# system.net
KiCad netlist of a schematic drawn in Altium Designer
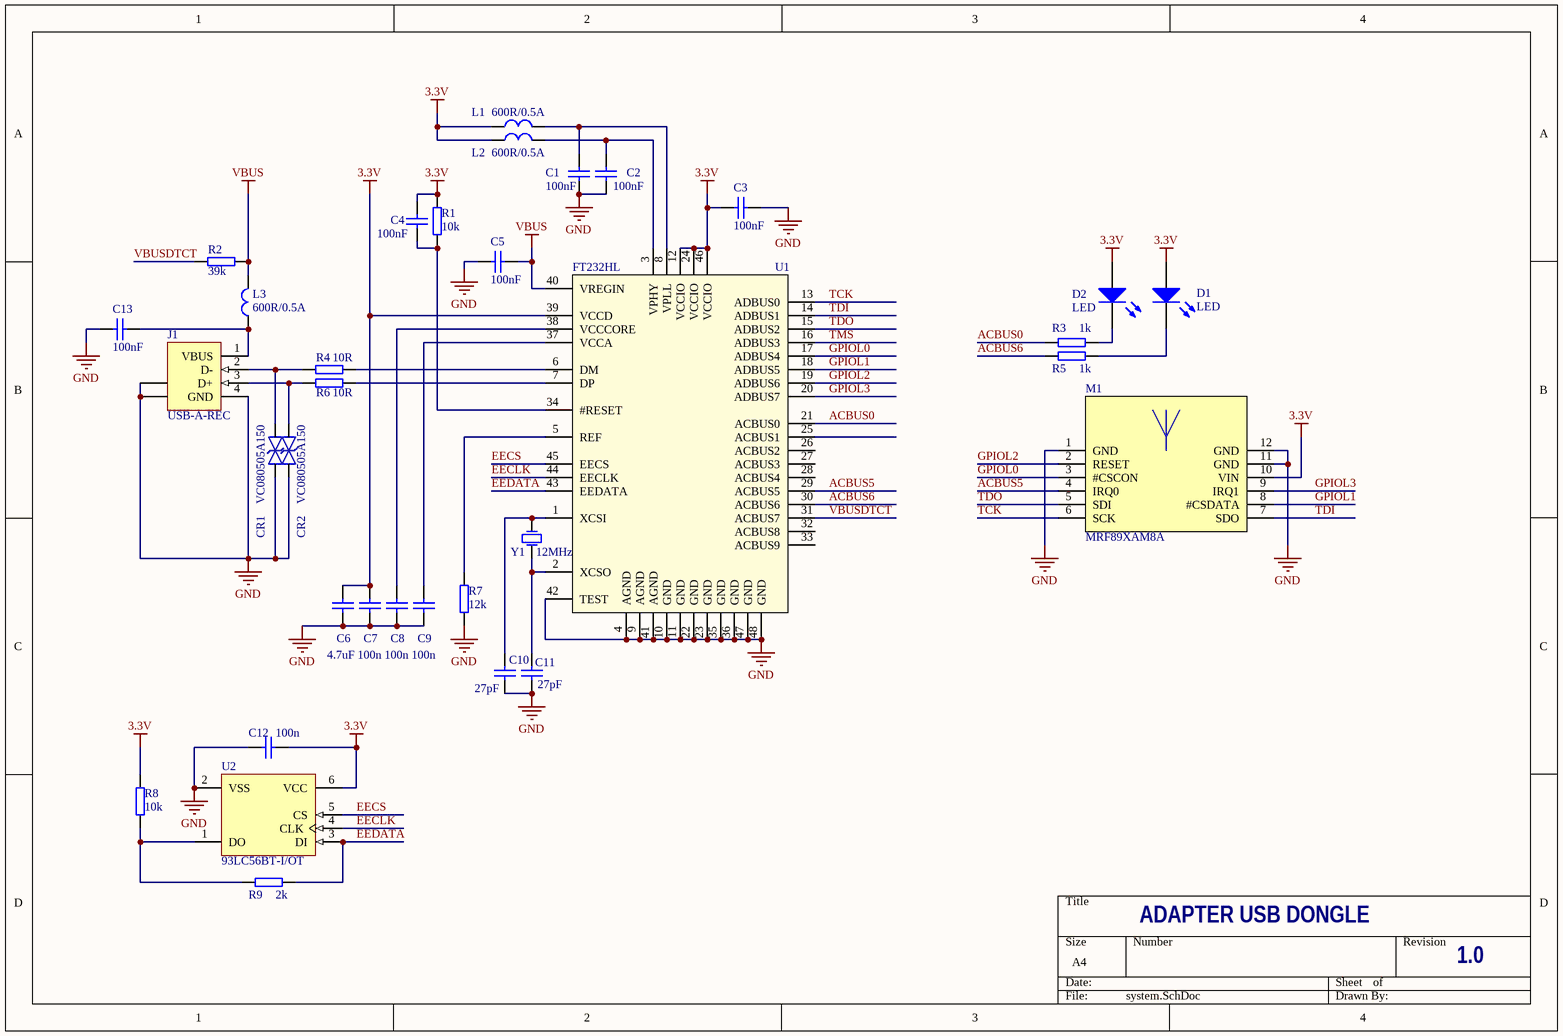
[diagram p0: system.SchDoc]

(export (version "E")
  (design (tool "Eeschema 10.0.6"))
  (components
    (comp (ref "C1")
      (value "100nF")
      (footprint "C0805")
      (description "Capacitor")
      (fields (field (name "PUBLISHER") "Altium Limited"))
      (libsource (lib "ANY Devices") (part "Cap"))
    )
    (comp (ref "C2")
      (value "100nF")
      (footprint "C0805")
      (description "Capacitor")
      (fields (field (name "PUBLISHER") "Altium Limited"))
      (libsource (lib "ANY Devices") (part "Cap"))
    )
    (comp (ref "C3")
      (value "100nF")
      (footprint "C0805")
      (description "Capacitor")
      (fields (field (name "PUBLISHER") "Altium Limited"))
      (libsource (lib "ANY Devices") (part "Cap"))
    )
    (comp (ref "C4")
      (value "100nF")
      (footprint "C0805")
      (description "Capacitor")
      (fields (field (name "PUBLISHER") "Altium Limited"))
      (libsource (lib "ANY Devices") (part "Cap"))
    )
    (comp (ref "C5")
      (value "100nF")
      (footprint "C0805")
      (description "Capacitor")
      (fields (field (name "PUBLISHER") "Altium Limited"))
      (libsource (lib "ANY Devices") (part "Cap"))
    )
    (comp (ref "C6")
      (value "4.7uF")
      (footprint "C0805")
      (description "Capacitor")
      (fields (field (name "PUBLISHER") "Altium Limited"))
      (libsource (lib "ANY Devices") (part "Cap"))
    )
    (comp (ref "C7")
      (value "100n")
      (footprint "C0805")
      (description "Capacitor")
      (fields (field (name "PUBLISHER") "Altium Limited"))
      (libsource (lib "ANY Devices") (part "Cap"))
    )
    (comp (ref "C8")
      (value "100n")
      (footprint "C0805")
      (description "Capacitor")
      (fields (field (name "PUBLISHER") "Altium Limited"))
      (libsource (lib "ANY Devices") (part "Cap"))
    )
    (comp (ref "C9")
      (value "100n")
      (footprint "C0805")
      (description "Capacitor")
      (fields (field (name "PUBLISHER") "Altium Limited"))
      (libsource (lib "ANY Devices") (part "Cap"))
    )
    (comp (ref "C10")
      (value "27pF")
      (footprint "C0805")
      (description "Capacitor")
      (fields (field (name "PUBLISHER") "Altium Limited"))
      (libsource (lib "ANY Devices") (part "Cap"))
    )
    (comp (ref "C11")
      (value "27pF")
      (footprint "C0805")
      (description "Capacitor")
      (fields (field (name "PUBLISHER") "Altium Limited"))
      (libsource (lib "ANY Devices") (part "Cap"))
    )
    (comp (ref "C12")
      (value "100n")
      (footprint "C0805")
      (description "Capacitor")
      (fields (field (name "PUBLISHER") "Altium Limited"))
      (libsource (lib "ANY Devices") (part "Cap"))
    )
    (comp (ref "C13")
      (value "100nF")
      (footprint "C0805")
      (description "Capacitor")
      (fields (field (name "Comment") "10nF") (field (name "PUBLISHER") "Altium Limited"))
      (libsource (lib "ANY Devices") (part "Cap"))
    )
    (comp (ref "CR1")
      (value "VC080505A150")
      (footprint "R0805")
      (description "Multilayer Ceramic Transient Voltage Suppressors")
      (libsource (lib "ANY Devices") (part "ESD Protection"))
    )
    (comp (ref "CR2")
      (value "VC080505A150")
      (footprint "R0805")
      (description "Multilayer Ceramic Transient Voltage Suppressors")
      (libsource (lib "ANY Devices") (part "ESD Protection"))
    )
    (comp (ref "D1")
      (value "LED")
      (footprint "D0805")
      (description "Typical RED, GREEN, YELLOW, AMBER GaAs LED")
      (fields (field (name "PUBLISHER") "Altium Limited"))
      (libsource (lib "ANY Devices") (part "LED2"))
    )
    (comp (ref "D2")
      (value "LED")
      (footprint "D0805")
      (description "Typical RED, GREEN, YELLOW, AMBER GaAs LED")
      (fields (field (name "PUBLISHER") "Altium Limited"))
      (libsource (lib "ANY Devices") (part "LED2"))
    )
    (comp (ref "J1")
      (value "USB-A-REC")
      (footprint "USB/SM2.5-4H4A")
      (description "USB 1.1, Right Angle, Thru-Hole, Reverse Type, 4 Position, Black")
      (libsource (lib "ANY Connectors") (part "USB-A_MALE"))
    )
    (comp (ref "L1")
      (value "600R/0.5A")
      (footprint "L0805")
      (description "Inductor Ferrite Bead, BLM18PG")
      (fields (field (name "PUBLISHER") "Altium Limited"))
      (libsource (lib "ANY Devices") (part "Inductor Ferrite Bead"))
    )
    (comp (ref "L2")
      (value "600R/0.5A")
      (footprint "L0805")
      (description "Inductor Ferrite Bead, BLM18PG")
      (fields (field (name "PUBLISHER") "Altium Limited"))
      (libsource (lib "ANY Devices") (part "Inductor Ferrite Bead"))
    )
    (comp (ref "L3")
      (value "600R/0.5A")
      (footprint "L0805")
      (description "Inductor Ferrite Bead, BLM18PG")
      (fields (field (name "PUBLISHER") "Altium Limited"))
      (libsource (lib "ANY Devices") (part "Inductor Ferrite Bead"))
    )
    (comp (ref "M1")
      (value "MRF89XAM8A")
      (footprint "MRF89XAM8A")
      (description "868 MHz Ultra-Low Power  Sub-GHz Transceiver Module")
      (libsource (lib "Modules") (part "MRF89XAM8A"))
    )
    (comp (ref "R1")
      (value "10k")
      (footprint "R0805")
      (description "Resistor")
      (fields (field (name "PUBLISHER") "Altium Limited"))
      (libsource (lib "") (part "Res2_1"))
    )
    (comp (ref "R2")
      (value "39k")
      (footprint "R0805")
      (description "Resistor")
      (fields (field (name "PUBLISHER") "Altium Limited"))
      (libsource (lib "ANY Devices") (part "Res2"))
    )
    (comp (ref "R3")
      (value "1k")
      (footprint "R0805")
      (description "Resistor")
      (fields (field (name "PUBLISHER") "Altium Limited"))
      (libsource (lib "") (part "Res2_2"))
    )
    (comp (ref "R4")
      (value "10R")
      (footprint "R0805")
      (description "Resistor")
      (fields (field (name "PUBLISHER") "Altium Limited"))
      (libsource (lib "") (part "Res2_2"))
    )
    (comp (ref "R5")
      (value "1k")
      (footprint "R0805")
      (description "Resistor")
      (fields (field (name "PUBLISHER") "Altium Limited"))
      (libsource (lib "") (part "Res2_2"))
    )
    (comp (ref "R6")
      (value "10R")
      (footprint "R0805")
      (description "Resistor")
      (fields (field (name "PUBLISHER") "Altium Limited"))
      (libsource (lib "") (part "Res2_1"))
    )
    (comp (ref "R7")
      (value "12k")
      (footprint "R0805")
      (description "Resistor")
      (fields (field (name "PUBLISHER") "Altium Limited"))
      (libsource (lib "") (part "Res2_1"))
    )
    (comp (ref "R8")
      (value "10k")
      (footprint "R0805")
      (description "Resistor")
      (fields (field (name "PUBLISHER") "Altium Limited"))
      (libsource (lib "") (part "Res2_1"))
    )
    (comp (ref "R9")
      (value "2k")
      (footprint "R0805")
      (description "Resistor")
      (fields (field (name "PUBLISHER") "Altium Limited"))
      (libsource (lib "ANY Devices") (part "Res2"))
    )
    (comp (ref "U1")
      (value "FT232HL")
      (footprint "LQFP-48_M")
      (description "Single Channel HiSpeed USB to Multipurpose   UART/FIFO IC")
      (libsource (lib "ANYlib") (part "FT232HL"))
    )
    (comp (ref "U2")
      (value "93LC56BT-I/OT")
      (footprint "SOT-23-OT6_N")
      (description "2K, 128x16-bit, 2.5V Microwire Serial EEPROM, 6-Pin SOT-23, Industrial Temperature, Tape and Reel")
      (fields (field (name "PUBLISHER") "Altium Limited"))
      (libsource (lib "ANYlib") (part "93LC56BT-I/OT"))
    )
    (comp (ref "Y1")
      (value "12MHz")
      (footprint "OSC 5.0X3.2")
      (description "Crystal")
      (fields (field (name "PUBLISHER") "Altium Limited"))
      (libsource (lib "ANY Devices") (part "XTAL_ABM3"))
    )
  )
  (nets
    (net (code "1") (name "/ACBUS0") (class "Default")
      (node (ref "R3") (pin "1") (pinfunction "1_1") (pintype "passive"))
      (node (ref "U1") (pin "21") (pinfunction "ACBUS0_21") (pintype "passive"))
    )
    (net (code "2") (name "/ACBUS5") (class "Default")
      (node (ref "M1") (pin "4") (pinfunction "IRQ0_4") (pintype "passive"))
      (node (ref "U1") (pin "29") (pinfunction "ACBUS5_29") (pintype "passive"))
    )
    (net (code "3") (name "/ACBUS6") (class "Default")
      (node (ref "R5") (pin "1") (pinfunction "1_1") (pintype "passive"))
      (node (ref "U1") (pin "30") (pinfunction "ACBUS6_30") (pintype "passive"))
    )
    (net (code "4") (name "/EECLK") (class "Default")
      (node (ref "U1") (pin "44") (pinfunction "EECLK_44") (pintype "passive"))
      (node (ref "U2") (pin "4") (pinfunction "CLK_4") (pintype "input"))
    )
    (net (code "5") (name "/EECS") (class "Default")
      (node (ref "U1") (pin "45") (pinfunction "EECS_45") (pintype "passive"))
      (node (ref "U2") (pin "5") (pinfunction "CS_5") (pintype "input"))
    )
    (net (code "6") (name "/EEDATA") (class "Default")
      (node (ref "R9") (pin "1") (pinfunction "1_1") (pintype "passive"))
      (node (ref "U1") (pin "43") (pinfunction "EEDATA_43") (pintype "passive"))
      (node (ref "U2") (pin "3") (pinfunction "DI_3") (pintype "input"))
    )
    (net (code "7") (name "/GPIOL0") (class "Default")
      (node (ref "M1") (pin "3") (pinfunction "#CSCON_3") (pintype "passive"))
      (node (ref "U1") (pin "17") (pinfunction "ADBUS4_17") (pintype "passive"))
    )
    (net (code "8") (name "/GPIOL1") (class "Default")
      (node (ref "M1") (pin "8") (pinfunction "#CSDATA_8") (pintype "passive"))
      (node (ref "U1") (pin "18") (pinfunction "ADBUS5_18") (pintype "passive"))
    )
    (net (code "9") (name "/GPIOL2") (class "Default")
      (node (ref "M1") (pin "2") (pinfunction "RESET_2") (pintype "passive"))
      (node (ref "U1") (pin "19") (pinfunction "ADBUS6_19") (pintype "passive"))
    )
    (net (code "10") (name "/GPIOL3") (class "Default")
      (node (ref "M1") (pin "9") (pinfunction "IRQ1_9") (pintype "passive"))
      (node (ref "U1") (pin "20") (pinfunction "ADBUS7_20") (pintype "passive"))
    )
    (net (code "11") (name "/TCK") (class "Default")
      (node (ref "M1") (pin "6") (pinfunction "SCK_6") (pintype "passive"))
      (node (ref "U1") (pin "13") (pinfunction "ADBUS0_13") (pintype "passive"))
    )
    (net (code "12") (name "/TDI") (class "Default")
      (node (ref "M1") (pin "7") (pinfunction "SDO_7") (pintype "passive"))
      (node (ref "U1") (pin "14") (pinfunction "ADBUS1_14") (pintype "passive"))
    )
    (net (code "13") (name "/TDO") (class "Default")
      (node (ref "M1") (pin "5") (pinfunction "SDI_5") (pintype "passive"))
      (node (ref "U1") (pin "15") (pinfunction "ADBUS2_15") (pintype "passive"))
    )
    (net (code "14") (name "/TMS") (class "Default")
      (node (ref "U1") (pin "16") (pinfunction "ADBUS3_16") (pintype "passive"))
    )
    (net (code "15") (name "/VBUSDTCT") (class "Default")
      (node (ref "R2") (pin "2") (pinfunction "2_2") (pintype "passive"))
      (node (ref "U1") (pin "31") (pinfunction "ACBUS7_31") (pintype "passive"))
    )
    (net (code "16") (name "3.3V") (class "Default")
      (node (ref "C12") (pin "2") (pinfunction "2_2") (pintype "passive"))
      (node (ref "C3") (pin "2") (pinfunction "2_2") (pintype "passive"))
      (node (ref "C4") (pin "1") (pinfunction "1_1") (pintype "passive"))
      (node (ref "C6") (pin "1") (pinfunction "1_1") (pintype "passive"))
      (node (ref "C7") (pin "1") (pinfunction "1_1") (pintype "passive"))
      (node (ref "D1") (pin "1") (pinfunction "A_1") (pintype "passive"))
      (node (ref "D2") (pin "1") (pinfunction "A_1") (pintype "passive"))
      (node (ref "L1") (pin "1") (pinfunction "1_1") (pintype "passive"))
      (node (ref "L2") (pin "1") (pinfunction "1_1") (pintype "passive"))
      (node (ref "M1") (pin "10") (pinfunction "VIN_10") (pintype "passive"))
      (node (ref "R1") (pin "2") (pinfunction "2_2") (pintype "passive"))
      (node (ref "R8") (pin "2") (pinfunction "2_2") (pintype "passive"))
      (node (ref "U1") (pin "12") (pinfunction "VCCIO_12") (pintype "passive"))
      (node (ref "U1") (pin "24") (pinfunction "VCCIO_24") (pintype "passive"))
      (node (ref "U1") (pin "39") (pinfunction "VCCD_39") (pintype "passive"))
      (node (ref "U1") (pin "46") (pinfunction "VCCIO_46") (pintype "passive"))
      (node (ref "U2") (pin "6") (pinfunction "VCC_6") (pintype "power_in"))
    )
    (net (code "17") (name "GND") (class "Default")
      (node (ref "C1") (pin "2") (pinfunction "2_2") (pintype "passive"))
      (node (ref "C10") (pin "2") (pinfunction "2_2") (pintype "passive"))
      (node (ref "C11") (pin "2") (pinfunction "2_2") (pintype "passive"))
      (node (ref "C12") (pin "1") (pinfunction "1_1") (pintype "passive"))
      (node (ref "C13") (pin "1") (pinfunction "1_1") (pintype "passive"))
      (node (ref "C2") (pin "2") (pinfunction "2_2") (pintype "passive"))
      (node (ref "C3") (pin "1") (pinfunction "1_1") (pintype "passive"))
      (node (ref "C5") (pin "2") (pinfunction "2_2") (pintype "passive"))
      (node (ref "C6") (pin "2") (pinfunction "2_2") (pintype "passive"))
      (node (ref "C7") (pin "2") (pinfunction "2_2") (pintype "passive"))
      (node (ref "C8") (pin "2") (pinfunction "2_2") (pintype "passive"))
      (node (ref "C9") (pin "2") (pinfunction "2_2") (pintype "passive"))
      (node (ref "CR1") (pin "1") (pinfunction "1_1") (pintype "passive"))
      (node (ref "CR2") (pin "1") (pinfunction "1_1") (pintype "passive"))
      (node (ref "J1") (pin "4") (pinfunction "GND_4") (pintype "power_in"))
      (node (ref "J1") (pin "5") (pinfunction "SHLD_5") (pintype "passive"))
      (node (ref "J1") (pin "6") (pinfunction "SHLD_6") (pintype "passive"))
      (node (ref "M1") (pin "1") (pinfunction "GND_1") (pintype "passive"))
      (node (ref "M1") (pin "11") (pinfunction "GND_11") (pintype "passive"))
      (node (ref "M1") (pin "12") (pinfunction "GND_12") (pintype "passive"))
      (node (ref "R7") (pin "1") (pinfunction "1_1") (pintype "passive"))
      (node (ref "U1") (pin "10") (pinfunction "GND_10") (pintype "passive"))
      (node (ref "U1") (pin "11") (pinfunction "GND_11") (pintype "passive"))
      (node (ref "U1") (pin "22") (pinfunction "GND_22") (pintype "passive"))
      (node (ref "U1") (pin "23") (pinfunction "GND_23") (pintype "passive"))
      (node (ref "U1") (pin "35") (pinfunction "GND_35") (pintype "passive"))
      (node (ref "U1") (pin "36") (pinfunction "GND_36") (pintype "passive"))
      (node (ref "U1") (pin "4") (pinfunction "AGND_4") (pintype "passive"))
      (node (ref "U1") (pin "41") (pinfunction "AGND_41") (pintype "passive"))
      (node (ref "U1") (pin "42") (pinfunction "TEST_42") (pintype "passive"))
      (node (ref "U1") (pin "47") (pinfunction "GND_47") (pintype "passive"))
      (node (ref "U1") (pin "48") (pinfunction "GND_48") (pintype "passive"))
      (node (ref "U1") (pin "9") (pinfunction "AGND_9") (pintype "passive"))
      (node (ref "U2") (pin "2") (pinfunction "VSS_2") (pintype "power_in"))
    )
    (net (code "18") (name "Net-(D1-K)") (class "Default")
      (node (ref "D1") (pin "2") (pinfunction "K_2") (pintype "passive"))
      (node (ref "R5") (pin "2") (pinfunction "2_2") (pintype "passive"))
    )
    (net (code "19") (name "Net-(D2-K)") (class "Default")
      (node (ref "D2") (pin "2") (pinfunction "K_2") (pintype "passive"))
      (node (ref "R3") (pin "2") (pinfunction "2_2") (pintype "passive"))
    )
    (net (code "20") (name "Net-(J1-D+)") (class "Default")
      (node (ref "CR2") (pin "2") (pinfunction "2_2") (pintype "passive"))
      (node (ref "J1") (pin "3") (pinfunction "D+_3") (pintype "input"))
      (node (ref "R6") (pin "1") (pinfunction "1_1") (pintype "passive"))
    )
    (net (code "21") (name "Net-(J1-D-)") (class "Default")
      (node (ref "CR1") (pin "2") (pinfunction "2_2") (pintype "passive"))
      (node (ref "J1") (pin "2") (pinfunction "D-_2") (pintype "input"))
      (node (ref "R4") (pin "1") (pinfunction "1_1") (pintype "passive"))
    )
    (net (code "22") (name "Net-(J1-VBUS)") (class "Default")
      (node (ref "C13") (pin "2") (pinfunction "2_2") (pintype "passive"))
      (node (ref "J1") (pin "1") (pinfunction "VBUS_1") (pintype "power_in"))
      (node (ref "L3") (pin "1") (pinfunction "1_1") (pintype "passive"))
    )
    (net (code "23") (name "Net-(U1-#RESET)") (class "Default")
      (node (ref "C4") (pin "2") (pinfunction "2_2") (pintype "passive"))
      (node (ref "R1") (pin "1") (pinfunction "1_1") (pintype "passive"))
      (node (ref "U1") (pin "34") (pinfunction "#RESET_34") (pintype "passive"))
    )
    (net (code "24") (name "Net-(U1-DM)") (class "Default")
      (node (ref "R4") (pin "2") (pinfunction "2_2") (pintype "passive"))
      (node (ref "U1") (pin "6") (pinfunction "DM_6") (pintype "passive"))
    )
    (net (code "25") (name "Net-(U1-DP)") (class "Default")
      (node (ref "R6") (pin "2") (pinfunction "2_2") (pintype "passive"))
      (node (ref "U1") (pin "7") (pinfunction "DP_7") (pintype "passive"))
    )
    (net (code "26") (name "Net-(U1-REF)") (class "Default")
      (node (ref "R7") (pin "2") (pinfunction "2_2") (pintype "passive"))
      (node (ref "U1") (pin "5") (pinfunction "REF_5") (pintype "passive"))
    )
    (net (code "27") (name "Net-(U1-VCCA)") (class "Default")
      (node (ref "C9") (pin "1") (pinfunction "1_1") (pintype "passive"))
      (node (ref "U1") (pin "37") (pinfunction "VCCA_37") (pintype "passive"))
    )
    (net (code "28") (name "Net-(U1-VCCCORE)") (class "Default")
      (node (ref "C8") (pin "1") (pinfunction "1_1") (pintype "passive"))
      (node (ref "U1") (pin "38") (pinfunction "VCCCORE_38") (pintype "passive"))
    )
    (net (code "29") (name "Net-(U1-VPHY)") (class "Default")
      (node (ref "C2") (pin "1") (pinfunction "1_1") (pintype "passive"))
      (node (ref "L2") (pin "2") (pinfunction "2_2") (pintype "passive"))
      (node (ref "U1") (pin "3") (pinfunction "VPHY_3") (pintype "passive"))
    )
    (net (code "30") (name "Net-(U1-VPLL)") (class "Default")
      (node (ref "C1") (pin "1") (pinfunction "1_1") (pintype "passive"))
      (node (ref "L1") (pin "2") (pinfunction "2_2") (pintype "passive"))
      (node (ref "U1") (pin "8") (pinfunction "VPLL_8") (pintype "passive"))
    )
    (net (code "31") (name "Net-(U1-XCSI)") (class "Default")
      (node (ref "C10") (pin "1") (pinfunction "1_1") (pintype "passive"))
      (node (ref "U1") (pin "1") (pinfunction "XCSI_1") (pintype "passive"))
      (node (ref "Y1") (pin "3") (pinfunction "OSC2_3") (pintype "passive"))
    )
    (net (code "32") (name "Net-(U1-XCSO)") (class "Default")
      (node (ref "C11") (pin "1") (pinfunction "1_1") (pintype "passive"))
      (node (ref "U1") (pin "2") (pinfunction "XCSO_2") (pintype "passive"))
      (node (ref "Y1") (pin "1") (pinfunction "OSC1_1") (pintype "passive"))
    )
    (net (code "33") (name "Net-(U2-DO)") (class "Default")
      (node (ref "R8") (pin "1") (pinfunction "1_1") (pintype "passive"))
      (node (ref "R9") (pin "2") (pinfunction "2_2") (pintype "passive"))
      (node (ref "U2") (pin "1") (pinfunction "DO_1") (pintype "tri_state"))
    )
    (net (code "34") (name "VBUS") (class "Default")
      (node (ref "C5") (pin "1") (pinfunction "1_1") (pintype "passive"))
      (node (ref "L3") (pin "2") (pinfunction "2_2") (pintype "passive"))
      (node (ref "R2") (pin "1") (pinfunction "1_1") (pintype "passive"))
      (node (ref "U1") (pin "40") (pinfunction "VREGIN_40") (pintype "passive"))
    )
    (net (code "35") (name "unconnected-(U1-ACBUS1-Pad25)") (class "Default")
      (node (ref "U1") (pin "25") (pinfunction "ACBUS1_25") (pintype "passive"))
    )
    (net (code "36") (name "unconnected-(U1-ACBUS2-Pad26)") (class "Default")
      (node (ref "U1") (pin "26") (pinfunction "ACBUS2_26") (pintype "passive"))
    )
    (net (code "37") (name "unconnected-(U1-ACBUS3-Pad27)") (class "Default")
      (node (ref "U1") (pin "27") (pinfunction "ACBUS3_27") (pintype "passive"))
    )
    (net (code "38") (name "unconnected-(U1-ACBUS4-Pad28)") (class "Default")
      (node (ref "U1") (pin "28") (pinfunction "ACBUS4_28") (pintype "passive"))
    )
    (net (code "39") (name "unconnected-(U1-ACBUS8-Pad32)") (class "Default")
      (node (ref "U1") (pin "32") (pinfunction "ACBUS8_32") (pintype "passive"))
    )
    (net (code "40") (name "unconnected-(U1-ACBUS9-Pad33)") (class "Default")
      (node (ref "U1") (pin "33") (pinfunction "ACBUS9_33") (pintype "passive"))
    )
  )
)
